# Mini_USB_Socket.net
KiCad netlist of a schematic drawn in Altium Designer
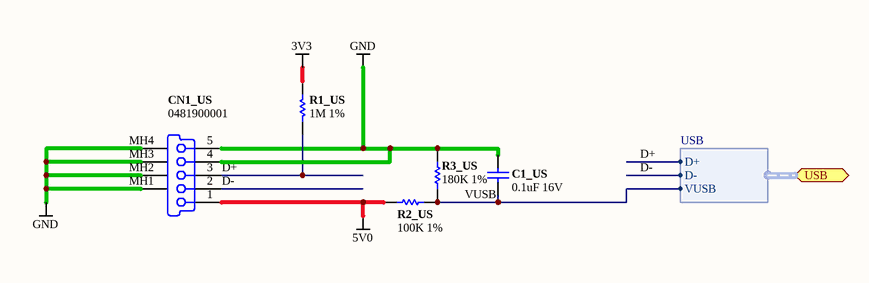
[diagram p0: Mini_USB_Socket.SchDoc]

(export (version "E")
  (design (tool "Eeschema 10.0.6"))
  (components
    (comp (ref "C1_US")
      (value "0.1uF 16V")
      (footprint "CAPC1005-STAR")
      (description "Capacitor, Ceramic, 0.1uF 10% 16V 0402 (1005) X7R")
      (fields (field (name "TOLERANCE") "10 %"))
      (libsource (lib "AltiumDesignLibrary") (part "CAP-NP"))
    )
    (comp (ref "CN1_US")
      (value "0481900001")
      (footprint "481900001")
      (libsource (lib "AltiumDesignLibrary") (part "0481900001"))
    )
    (comp (ref "R1_US")
      (value "1M 1%")
      (footprint "RESC1005-STAR")
      (description "Resistor, 1M 1% 0402")
      (fields (field (name "TOLERANCE") "%"))
      (libsource (lib "AltiumDesignLibrary") (part "RES"))
    )
    (comp (ref "R2_US")
      (value "100K 1%")
      (footprint "RESC1005-STAR")
      (description "Resistor, 100K 1% 0402 (1005)")
      (fields (field (name "TOLERANCE") "1 %"))
      (libsource (lib "AltiumDesignLibrary") (part "RES"))
    )
    (comp (ref "R3_US")
      (value "180K 1%")
      (footprint "RESC1005-STAR")
      (description "Resistor, 180K 1% 0402 (1005)")
      (fields (field (name "TOLERANCE") "%"))
      (libsource (lib "AltiumDesignLibrary") (part "RES"))
    )
  )
  (nets
    (net (code "2") (name "/D+") (class "Default")
      (node (ref "CN1_US") (pin "3") (pinfunction "3_3") (pintype "passive"))
      (node (ref "R1_US") (pin "1") (pinfunction "1_1") (pintype "passive"))
    )
    (net (code "3") (name "/D-") (class "Default")
      (node (ref "CN1_US") (pin "2") (pinfunction "2_2") (pintype "passive"))
    )
    (net (code "4") (name "/VUSB") (class "Default")
      (node (ref "C1_US") (pin "2") (pinfunction "2_2") (pintype "passive"))
      (node (ref "R2_US") (pin "1") (pinfunction "1_1") (pintype "passive"))
      (node (ref "R3_US") (pin "1") (pinfunction "1_1") (pintype "passive"))
    )
    (net (code "6") (name "3V3") (class "Default")
      (node (ref "R1_US") (pin "2") (pinfunction "2_2") (pintype "passive"))
    )
    (net (code "7") (name "5V0") (class "Default")
      (node (ref "CN1_US") (pin "1") (pinfunction "1_1") (pintype "passive"))
      (node (ref "R2_US") (pin "2") (pinfunction "2_2") (pintype "passive"))
    )
    (net (code "8") (name "GND") (class "Default")
      (node (ref "C1_US") (pin "1") (pinfunction "1_1") (pintype "passive"))
      (node (ref "CN1_US") (pin "4") (pinfunction "4_4") (pintype "passive"))
      (node (ref "CN1_US") (pin "5") (pinfunction "5_5") (pintype "passive"))
      (node (ref "CN1_US") (pin "MH1") (pinfunction "MH1_MH1") (pintype "passive"))
      (node (ref "CN1_US") (pin "MH2") (pinfunction "MH2_MH2") (pintype "passive"))
      (node (ref "CN1_US") (pin "MH3") (pinfunction "MH3_MH3") (pintype "passive"))
      (node (ref "CN1_US") (pin "MH4") (pinfunction "MH4_MH4") (pintype "passive"))
      (node (ref "R3_US") (pin "2") (pinfunction "2_2") (pintype "passive"))
    )
  )
)
